# GateDriverSketch.net
KiCad netlist of a schematic drawn in Altium Designer
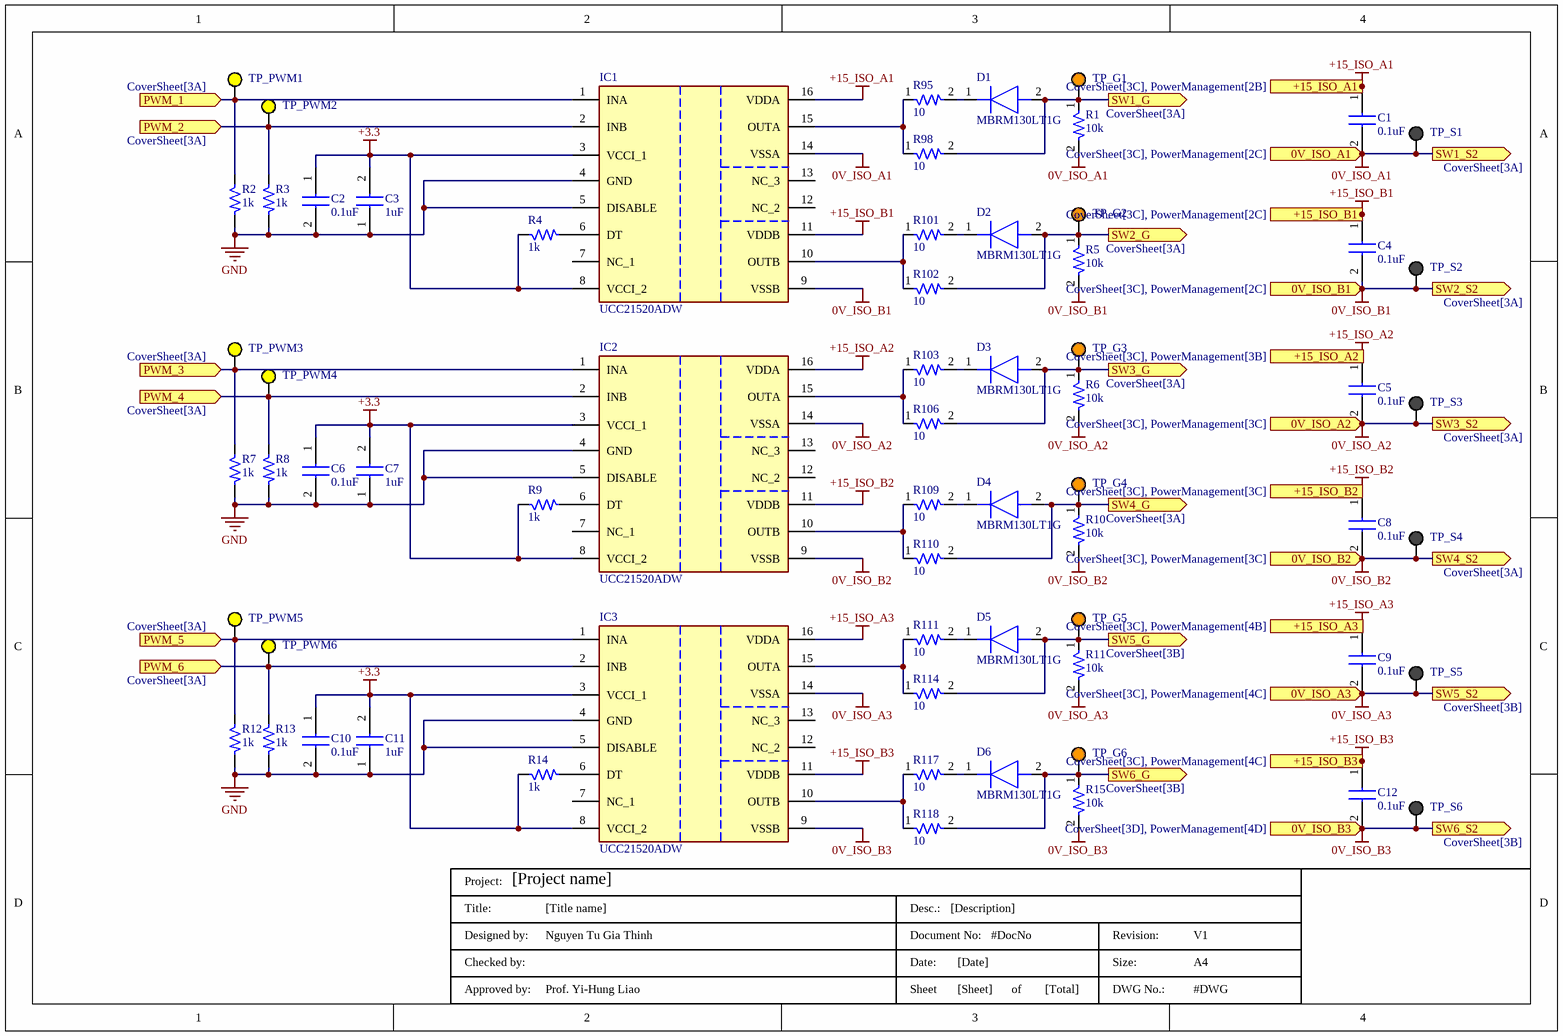
[diagram p0: GateDriverSketch.SchDoc]

(export (version "E")
  (design (tool "Eeschema 10.0.6"))
  (components
    (comp (ref "C1")
      (value "0.1uF")
      (footprint "SamacSys:C0805")
      (description "Capacitor")
      (fields
        (field (name "MANUFACTURER_PART_NUMBER") "C0805C104K3RACTU")
        (field (name "MOUSER PART NUMBER") "80-C0805C104K3R")
      )
      (libsource (lib "SamacSys") (part "C0805C104K3RACTU"))
    )
    (comp (ref "C2")
      (value "0.1uF")
      (footprint "SamacSys:C0805")
      (description "Capacitor")
      (fields
        (field (name "MANUFACTURER_PART_NUMBER") "C0805C104K3RACTU")
        (field (name "MOUSER PART NUMBER") "80-C0805C104K3R")
      )
      (libsource (lib "SamacSys") (part "C0805C104K3RACTU"))
    )
    (comp (ref "C3")
      (value "1uF")
      (footprint "CAPC2012X145N")
      (description "Capacitor")
      (fields
        (field (name "MANUFACTURER_PART_NUMBER") "GRM21BR71H105KA12L")
        (field (name "MOUSER PART NUMBER") "81-GRM21BR71H105KA2L")
      )
      (libsource (lib "ViennaRectifier") (part "GRM21BR71H105KA12L"))
    )
    (comp (ref "C4")
      (value "0.1uF")
      (footprint "SamacSys:C0805")
      (description "Capacitor")
      (fields
        (field (name "MANUFACTURER_PART_NUMBER") "C0805C104K3RACTU")
        (field (name "MOUSER PART NUMBER") "80-C0805C104K3R")
      )
      (libsource (lib "SamacSys") (part "C0805C104K3RACTU"))
    )
    (comp (ref "C5")
      (value "0.1uF")
      (footprint "SamacSys:C0805")
      (description "Capacitor")
      (fields
        (field (name "MANUFACTURER_PART_NUMBER") "C0805C104K3RACTU")
        (field (name "MOUSER PART NUMBER") "80-C0805C104K3R")
      )
      (libsource (lib "SamacSys") (part "C0805C104K3RACTU"))
    )
    (comp (ref "C6")
      (value "0.1uF")
      (footprint "SamacSys:C0805")
      (description "Capacitor")
      (fields
        (field (name "MANUFACTURER_PART_NUMBER") "C0805C104K3RACTU")
        (field (name "MOUSER PART NUMBER") "80-C0805C104K3R")
      )
      (libsource (lib "SamacSys") (part "C0805C104K3RACTU"))
    )
    (comp (ref "C7")
      (value "1uF")
      (footprint "CAPC2012X145N")
      (description "Capacitor")
      (fields
        (field (name "MANUFACTURER_PART_NUMBER") "GRM21BR71H105KA12L")
        (field (name "MOUSER PART NUMBER") "81-GRM21BR71H105KA2L")
      )
      (libsource (lib "ViennaRectifier") (part "GRM21BR71H105KA12L"))
    )
    (comp (ref "C8")
      (value "0.1uF")
      (footprint "SamacSys:C0805")
      (description "Capacitor")
      (fields
        (field (name "MANUFACTURER_PART_NUMBER") "C0805C104K3RACTU")
        (field (name "MOUSER PART NUMBER") "80-C0805C104K3R")
      )
      (libsource (lib "SamacSys") (part "C0805C104K3RACTU"))
    )
    (comp (ref "C9")
      (value "0.1uF")
      (footprint "SamacSys:C0805")
      (description "Capacitor")
      (fields
        (field (name "MANUFACTURER_PART_NUMBER") "C0805C104K3RACTU")
        (field (name "MOUSER PART NUMBER") "80-C0805C104K3R")
      )
      (libsource (lib "SamacSys") (part "C0805C104K3RACTU"))
    )
    (comp (ref "C10")
      (value "0.1uF")
      (footprint "SamacSys:C0805")
      (description "Capacitor")
      (fields
        (field (name "MANUFACTURER_PART_NUMBER") "C0805C104K3RACTU")
        (field (name "MOUSER PART NUMBER") "80-C0805C104K3R")
      )
      (libsource (lib "SamacSys") (part "C0805C104K3RACTU"))
    )
    (comp (ref "C11")
      (value "1uF")
      (footprint "CAPC2012X145N")
      (description "Capacitor")
      (fields
        (field (name "MANUFACTURER_PART_NUMBER") "GRM21BR71H105KA12L")
        (field (name "MOUSER PART NUMBER") "81-GRM21BR71H105KA2L")
      )
      (libsource (lib "ViennaRectifier") (part "GRM21BR71H105KA12L"))
    )
    (comp (ref "C12")
      (value "0.1uF")
      (footprint "SamacSys:C0805")
      (description "Capacitor")
      (fields
        (field (name "MANUFACTURER_PART_NUMBER") "C0805C104K3RACTU")
        (field (name "MOUSER PART NUMBER") "80-C0805C104K3R")
      )
      (libsource (lib "SamacSys") (part "C0805C104K3RACTU"))
    )
    (comp (ref "D1")
      (value "MBRM130LT1G")
      (footprint "SamacSys:MBRM130LT1G")
      (description "Diode")
      (fields (field (name "MOUSER PART NUMBER") "863-MBRM130LT1G"))
      (libsource (lib "SamacSys") (part "MBRM130LT1G"))
    )
    (comp (ref "D2")
      (value "MBRM130LT1G")
      (footprint "SamacSys:MBRM130LT1G")
      (description "Diode")
      (fields (field (name "MOUSER PART NUMBER") "863-MBRM130LT1G"))
      (libsource (lib "SamacSys") (part "MBRM130LT1G"))
    )
    (comp (ref "D3")
      (value "MBRM130LT1G")
      (footprint "SamacSys:MBRM130LT1G")
      (description "Diode")
      (fields (field (name "MOUSER PART NUMBER") "863-MBRM130LT1G"))
      (libsource (lib "SamacSys") (part "MBRM130LT1G"))
    )
    (comp (ref "D4")
      (value "MBRM130LT1G")
      (footprint "SamacSys:MBRM130LT1G")
      (description "Diode")
      (fields (field (name "MOUSER PART NUMBER") "863-MBRM130LT1G"))
      (libsource (lib "SamacSys") (part "MBRM130LT1G"))
    )
    (comp (ref "D5")
      (value "MBRM130LT1G")
      (footprint "SamacSys:MBRM130LT1G")
      (description "Diode")
      (fields (field (name "MOUSER PART NUMBER") "863-MBRM130LT1G"))
      (libsource (lib "SamacSys") (part "MBRM130LT1G"))
    )
    (comp (ref "D6")
      (value "MBRM130LT1G")
      (footprint "SamacSys:MBRM130LT1G")
      (description "Diode")
      (fields (field (name "MOUSER PART NUMBER") "863-MBRM130LT1G"))
      (libsource (lib "SamacSys") (part "MBRM130LT1G"))
    )
    (comp (ref "IC1")
      (value "UCC21520ADW")
      (footprint "SamacSys:SOIC127P1030X265-16N")
      (description "Integrated Circuit")
      (fields (field (name "MOUSER PART NUMBER") "595-UCC21520ADW"))
      (libsource (lib "ViennaRectifier") (part "UCC21520ADW"))
    )
    (comp (ref "IC2")
      (value "UCC21520ADW")
      (footprint "SamacSys:SOIC127P1030X265-16N")
      (description "Integrated Circuit")
      (fields (field (name "MOUSER PART NUMBER") "595-UCC21520ADW"))
      (libsource (lib "ViennaRectifier") (part "UCC21520ADW"))
    )
    (comp (ref "IC3")
      (value "UCC21520ADW")
      (footprint "SamacSys:SOIC127P1030X265-16N")
      (description "Integrated Circuit")
      (fields (field (name "MOUSER PART NUMBER") "595-UCC21520ADW"))
      (libsource (lib "ViennaRectifier") (part "UCC21520ADW"))
    )
    (comp (ref "R1")
      (value "10k")
      (footprint "RESC2012X50N")
      (description "Resistor")
      (fields
        (field (name "MANUFACTURER_PART_NUMBER") "CRCW0805470RFKEA")
        (field (name "MOUSER PART NUMBER") "71-CRCW0805-470-E3")
      )
      (libsource (lib "ViennaRectifier") (part "CRCW0805470RFKEA_1"))
    )
    (comp (ref "R2")
      (value "1k")
      (footprint "SM-1206")
      (description "Resistor 1/4W")
      (libsource (lib "ViennaRectifier") (part "R"))
    )
    (comp (ref "R3")
      (value "1k")
      (footprint "SM-1206")
      (description "Resistor 1/4W")
      (libsource (lib "ViennaRectifier") (part "R"))
    )
    (comp (ref "R4")
      (value "1k")
      (footprint "SM-1206")
      (description "Resistor 1/4W")
      (libsource (lib "ViennaRectifier") (part "R"))
    )
    (comp (ref "R5")
      (value "10k")
      (footprint "RESC2012X50N")
      (description "Resistor")
      (fields
        (field (name "MANUFACTURER_PART_NUMBER") "CRCW0805470RFKEA")
        (field (name "MOUSER PART NUMBER") "71-CRCW0805-470-E3")
      )
      (libsource (lib "ViennaRectifier") (part "CRCW0805470RFKEA_1"))
    )
    (comp (ref "R6")
      (value "10k")
      (footprint "RESC2012X50N")
      (description "Resistor")
      (fields
        (field (name "MANUFACTURER_PART_NUMBER") "CRCW0805470RFKEA")
        (field (name "MOUSER PART NUMBER") "71-CRCW0805-470-E3")
      )
      (libsource (lib "ViennaRectifier") (part "CRCW0805470RFKEA_1"))
    )
    (comp (ref "R7")
      (value "1k")
      (footprint "SM-1206")
      (description "Resistor 1/4W")
      (libsource (lib "ViennaRectifier") (part "R"))
    )
    (comp (ref "R8")
      (value "1k")
      (footprint "SM-1206")
      (description "Resistor 1/4W")
      (libsource (lib "ViennaRectifier") (part "R"))
    )
    (comp (ref "R9")
      (value "1k")
      (footprint "SM-1206")
      (description "Resistor 1/4W")
      (libsource (lib "ViennaRectifier") (part "R"))
    )
    (comp (ref "R10")
      (value "10k")
      (footprint "RESC2012X50N")
      (description "Resistor")
      (fields
        (field (name "MANUFACTURER_PART_NUMBER") "CRCW0805470RFKEA")
        (field (name "MOUSER PART NUMBER") "71-CRCW0805-470-E3")
      )
      (libsource (lib "ViennaRectifier") (part "CRCW0805470RFKEA_1"))
    )
    (comp (ref "R11")
      (value "10k")
      (footprint "RESC2012X50N")
      (description "Resistor")
      (fields
        (field (name "MANUFACTURER_PART_NUMBER") "CRCW0805470RFKEA")
        (field (name "MOUSER PART NUMBER") "71-CRCW0805-470-E3")
      )
      (libsource (lib "ViennaRectifier") (part "CRCW0805470RFKEA_1"))
    )
    (comp (ref "R12")
      (value "1k")
      (footprint "SM-1206")
      (description "Resistor 1/4W")
      (libsource (lib "ViennaRectifier") (part "R"))
    )
    (comp (ref "R13")
      (value "1k")
      (footprint "SM-1206")
      (description "Resistor 1/4W")
      (libsource (lib "ViennaRectifier") (part "R"))
    )
    (comp (ref "R14")
      (value "1k")
      (footprint "SM-1206")
      (description "Resistor 1/4W")
      (libsource (lib "ViennaRectifier") (part "R"))
    )
    (comp (ref "R15")
      (value "10k")
      (footprint "RESC2012X50N")
      (description "Resistor")
      (fields
        (field (name "MANUFACTURER_PART_NUMBER") "CRCW0805470RFKEA")
        (field (name "MOUSER PART NUMBER") "71-CRCW0805-470-E3")
      )
      (libsource (lib "ViennaRectifier") (part "CRCW0805470RFKEA_1"))
    )
    (comp (ref "R95")
      (value "10")
      (footprint "RESC2012X50N")
      (description "Resistor")
      (fields
        (field (name "MANUFACTURER_PART_NUMBER") "CRCW0805470RFKEA")
        (field (name "MOUSER PART NUMBER") "71-CRCW0805-470-E3")
      )
      (libsource (lib "ViennaRectifier") (part "CRCW0805470RFKEA_1"))
    )
    (comp (ref "R98")
      (value "10")
      (footprint "RESC2012X50N")
      (description "Resistor")
      (fields
        (field (name "MANUFACTURER_PART_NUMBER") "CRCW0805470RFKEA")
        (field (name "MOUSER PART NUMBER") "71-CRCW0805-470-E3")
      )
      (libsource (lib "ViennaRectifier") (part "CRCW0805470RFKEA_1"))
    )
    (comp (ref "R101")
      (value "10")
      (footprint "RESC2012X50N")
      (description "Resistor")
      (fields
        (field (name "MANUFACTURER_PART_NUMBER") "CRCW0805470RFKEA")
        (field (name "MOUSER PART NUMBER") "71-CRCW0805-470-E3")
      )
      (libsource (lib "ViennaRectifier") (part "CRCW0805470RFKEA_1"))
    )
    (comp (ref "R102")
      (value "10")
      (footprint "RESC2012X50N")
      (description "Resistor")
      (fields
        (field (name "MANUFACTURER_PART_NUMBER") "CRCW0805470RFKEA")
        (field (name "MOUSER PART NUMBER") "71-CRCW0805-470-E3")
      )
      (libsource (lib "ViennaRectifier") (part "CRCW0805470RFKEA_1"))
    )
    (comp (ref "R103")
      (value "10")
      (footprint "RESC2012X50N")
      (description "Resistor")
      (fields
        (field (name "MANUFACTURER_PART_NUMBER") "CRCW0805470RFKEA")
        (field (name "MOUSER PART NUMBER") "71-CRCW0805-470-E3")
      )
      (libsource (lib "ViennaRectifier") (part "CRCW0805470RFKEA_1"))
    )
    (comp (ref "R106")
      (value "10")
      (footprint "RESC2012X50N")
      (description "Resistor")
      (fields
        (field (name "MANUFACTURER_PART_NUMBER") "CRCW0805470RFKEA")
        (field (name "MOUSER PART NUMBER") "71-CRCW0805-470-E3")
      )
      (libsource (lib "ViennaRectifier") (part "CRCW0805470RFKEA_1"))
    )
    (comp (ref "R109")
      (value "10")
      (footprint "RESC2012X50N")
      (description "Resistor")
      (fields
        (field (name "MANUFACTURER_PART_NUMBER") "CRCW0805470RFKEA")
        (field (name "MOUSER PART NUMBER") "71-CRCW0805-470-E3")
      )
      (libsource (lib "ViennaRectifier") (part "CRCW0805470RFKEA_1"))
    )
    (comp (ref "R110")
      (value "10")
      (footprint "RESC2012X50N")
      (description "Resistor")
      (fields
        (field (name "MANUFACTURER_PART_NUMBER") "CRCW0805470RFKEA")
        (field (name "MOUSER PART NUMBER") "71-CRCW0805-470-E3")
      )
      (libsource (lib "ViennaRectifier") (part "CRCW0805470RFKEA_1"))
    )
    (comp (ref "R111")
      (value "10")
      (footprint "RESC2012X50N")
      (description "Resistor")
      (fields
        (field (name "MANUFACTURER_PART_NUMBER") "CRCW0805470RFKEA")
        (field (name "MOUSER PART NUMBER") "71-CRCW0805-470-E3")
      )
      (libsource (lib "ViennaRectifier") (part "CRCW0805470RFKEA_1"))
    )
    (comp (ref "R114")
      (value "10")
      (footprint "RESC2012X50N")
      (description "Resistor")
      (fields
        (field (name "MANUFACTURER_PART_NUMBER") "CRCW0805470RFKEA")
        (field (name "MOUSER PART NUMBER") "71-CRCW0805-470-E3")
      )
      (libsource (lib "ViennaRectifier") (part "CRCW0805470RFKEA_1"))
    )
    (comp (ref "R117")
      (value "10")
      (footprint "RESC2012X50N")
      (description "Resistor")
      (fields
        (field (name "MANUFACTURER_PART_NUMBER") "CRCW0805470RFKEA")
        (field (name "MOUSER PART NUMBER") "71-CRCW0805-470-E3")
      )
      (libsource (lib "ViennaRectifier") (part "CRCW0805470RFKEA_1"))
    )
    (comp (ref "R118")
      (value "10")
      (footprint "RESC2012X50N")
      (description "Resistor")
      (fields
        (field (name "MANUFACTURER_PART_NUMBER") "CRCW0805470RFKEA")
        (field (name "MOUSER PART NUMBER") "71-CRCW0805-470-E3")
      )
      (libsource (lib "ViennaRectifier") (part "CRCW0805470RFKEA_1"))
    )
    (comp (ref "TP_G1")
      (value "~")
      (footprint "5003")
      (description "Test Point Orrange, Multipurpose, TH")
      (libsource (lib "TestPointKeystone") (part "5003"))
    )
    (comp (ref "TP_G2")
      (value "~")
      (footprint "5003")
      (description "Test Point Orrange, Multipurpose, TH")
      (libsource (lib "TestPointKeystone") (part "5003"))
    )
    (comp (ref "TP_G3")
      (value "~")
      (footprint "5003")
      (description "Test Point Orrange, Multipurpose, TH")
      (libsource (lib "TestPointKeystone") (part "5003"))
    )
    (comp (ref "TP_G4")
      (value "~")
      (footprint "5003")
      (description "Test Point Orrange, Multipurpose, TH")
      (libsource (lib "TestPointKeystone") (part "5003"))
    )
    (comp (ref "TP_G5")
      (value "~")
      (footprint "5003")
      (description "Test Point Orrange, Multipurpose, TH")
      (libsource (lib "TestPointKeystone") (part "5003"))
    )
    (comp (ref "TP_G6")
      (value "~")
      (footprint "5003")
      (description "Test Point Orrange, Multipurpose, TH")
      (libsource (lib "TestPointKeystone") (part "5003"))
    )
    (comp (ref "TP_PWM1")
      (value "~")
      (footprint "5004")
      (description "Test Point Yellow, Multipurpose, TH")
      (libsource (lib "TestPointKeystone") (part "5004"))
    )
    (comp (ref "TP_PWM2")
      (value "~")
      (footprint "5004")
      (description "Test Point Yellow, Multipurpose, TH")
      (libsource (lib "TestPointKeystone") (part "5004"))
    )
    (comp (ref "TP_PWM3")
      (value "~")
      (footprint "5004")
      (description "Test Point Yellow, Multipurpose, TH")
      (libsource (lib "TestPointKeystone") (part "5004"))
    )
    (comp (ref "TP_PWM4")
      (value "~")
      (footprint "5004")
      (description "Test Point Yellow, Multipurpose, TH")
      (libsource (lib "TestPointKeystone") (part "5004"))
    )
    (comp (ref "TP_PWM5")
      (value "~")
      (footprint "5004")
      (description "Test Point Yellow, Multipurpose, TH")
      (libsource (lib "TestPointKeystone") (part "5004"))
    )
    (comp (ref "TP_PWM6")
      (value "~")
      (footprint "5004")
      (description "Test Point Yellow, Multipurpose, TH")
      (libsource (lib "TestPointKeystone") (part "5004"))
    )
    (comp (ref "TP_S1")
      (value "~")
      (footprint "5001")
      (description "Test Point Black, Multipurpose, TH")
      (libsource (lib "TestPointKeystone") (part "5001"))
    )
    (comp (ref "TP_S2")
      (value "~")
      (footprint "5001")
      (description "Test Point Black, Multipurpose, TH")
      (libsource (lib "TestPointKeystone") (part "5001"))
    )
    (comp (ref "TP_S3")
      (value "~")
      (footprint "5001")
      (description "Test Point Black, Multipurpose, TH")
      (libsource (lib "TestPointKeystone") (part "5001"))
    )
    (comp (ref "TP_S4")
      (value "~")
      (footprint "5001")
      (description "Test Point Black, Multipurpose, TH")
      (libsource (lib "TestPointKeystone") (part "5001"))
    )
    (comp (ref "TP_S5")
      (value "~")
      (footprint "5001")
      (description "Test Point Black, Multipurpose, TH")
      (libsource (lib "TestPointKeystone") (part "5001"))
    )
    (comp (ref "TP_S6")
      (value "~")
      (footprint "5001")
      (description "Test Point Black, Multipurpose, TH")
      (libsource (lib "TestPointKeystone") (part "5001"))
    )
  )
  (nets
    (net (code "2") (name "+15_ISO_A1") (class "Default")
      (node (ref "C1") (pin "1") (pinfunction "1_1") (pintype "passive"))
      (node (ref "IC1") (pin "16") (pinfunction "VDDA_16") (pintype "passive"))
    )
    (net (code "3") (name "+15_ISO_A2") (class "Default")
      (node (ref "C5") (pin "1") (pinfunction "1_1") (pintype "passive"))
      (node (ref "IC2") (pin "16") (pinfunction "VDDA_16") (pintype "passive"))
    )
    (net (code "4") (name "+15_ISO_A3") (class "Default")
      (node (ref "C9") (pin "1") (pinfunction "1_1") (pintype "passive"))
      (node (ref "IC3") (pin "16") (pinfunction "VDDA_16") (pintype "passive"))
    )
    (net (code "5") (name "+15_ISO_B1") (class "Default")
      (node (ref "C4") (pin "1") (pinfunction "1_1") (pintype "passive"))
      (node (ref "IC1") (pin "11") (pinfunction "VDDB_11") (pintype "passive"))
    )
    (net (code "6") (name "+15_ISO_B2") (class "Default")
      (node (ref "C8") (pin "1") (pinfunction "1_1") (pintype "passive"))
      (node (ref "IC2") (pin "11") (pinfunction "VDDB_11") (pintype "passive"))
    )
    (net (code "7") (name "+15_ISO_B3") (class "Default")
      (node (ref "C12") (pin "1") (pinfunction "1_1") (pintype "passive"))
      (node (ref "IC3") (pin "11") (pinfunction "VDDB_11") (pintype "passive"))
    )
    (net (code "8") (name "/PWM_1") (class "Default")
      (node (ref "IC1") (pin "1") (pinfunction "INA_1") (pintype "passive"))
      (node (ref "R2") (pin "1") (pinfunction "1_1") (pintype "passive"))
      (node (ref "TP_PWM1") (pin "1") (pinfunction "1_1") (pintype "passive"))
    )
    (net (code "9") (name "/PWM_2") (class "Default")
      (node (ref "IC1") (pin "2") (pinfunction "INB_2") (pintype "passive"))
      (node (ref "R3") (pin "1") (pinfunction "1_1") (pintype "passive"))
      (node (ref "TP_PWM2") (pin "1") (pinfunction "1_1") (pintype "passive"))
    )
    (net (code "10") (name "/PWM_3") (class "Default")
      (node (ref "IC2") (pin "1") (pinfunction "INA_1") (pintype "passive"))
      (node (ref "R7") (pin "1") (pinfunction "1_1") (pintype "passive"))
      (node (ref "TP_PWM3") (pin "1") (pinfunction "1_1") (pintype "passive"))
    )
    (net (code "11") (name "/PWM_4") (class "Default")
      (node (ref "IC2") (pin "2") (pinfunction "INB_2") (pintype "passive"))
      (node (ref "R8") (pin "1") (pinfunction "1_1") (pintype "passive"))
      (node (ref "TP_PWM4") (pin "1") (pinfunction "1_1") (pintype "passive"))
    )
    (net (code "12") (name "/PWM_5") (class "Default")
      (node (ref "IC3") (pin "1") (pinfunction "INA_1") (pintype "passive"))
      (node (ref "R12") (pin "1") (pinfunction "1_1") (pintype "passive"))
      (node (ref "TP_PWM5") (pin "1") (pinfunction "1_1") (pintype "passive"))
    )
    (net (code "13") (name "/PWM_6") (class "Default")
      (node (ref "IC3") (pin "2") (pinfunction "INB_2") (pintype "passive"))
      (node (ref "R13") (pin "1") (pinfunction "1_1") (pintype "passive"))
      (node (ref "TP_PWM6") (pin "1") (pinfunction "1_1") (pintype "passive"))
    )
    (net (code "14") (name "/SW1_G") (class "Default")
      (node (ref "D1") (pin "2") (pinfunction "A_2") (pintype "passive"))
      (node (ref "R1") (pin "1") (pinfunction "1_1") (pintype "passive"))
      (node (ref "R98") (pin "2") (pinfunction "2_2") (pintype "passive"))
      (node (ref "TP_G1") (pin "1") (pinfunction "1_1") (pintype "passive"))
    )
    (net (code "15") (name "/SW2_G") (class "Default")
      (node (ref "D2") (pin "2") (pinfunction "A_2") (pintype "passive"))
      (node (ref "R102") (pin "2") (pinfunction "2_2") (pintype "passive"))
      (node (ref "R5") (pin "1") (pinfunction "1_1") (pintype "passive"))
      (node (ref "TP_G2") (pin "1") (pinfunction "1_1") (pintype "passive"))
    )
    (net (code "16") (name "/SW3_G") (class "Default")
      (node (ref "D3") (pin "2") (pinfunction "A_2") (pintype "passive"))
      (node (ref "R106") (pin "2") (pinfunction "2_2") (pintype "passive"))
      (node (ref "R6") (pin "1") (pinfunction "1_1") (pintype "passive"))
      (node (ref "TP_G3") (pin "1") (pinfunction "1_1") (pintype "passive"))
    )
    (net (code "17") (name "/SW4_G") (class "Default")
      (node (ref "D4") (pin "2") (pinfunction "A_2") (pintype "passive"))
      (node (ref "R10") (pin "1") (pinfunction "1_1") (pintype "passive"))
      (node (ref "R110") (pin "2") (pinfunction "2_2") (pintype "passive"))
      (node (ref "TP_G4") (pin "1") (pinfunction "1_1") (pintype "passive"))
    )
    (net (code "18") (name "/SW5_G") (class "Default")
      (node (ref "D5") (pin "2") (pinfunction "A_2") (pintype "passive"))
      (node (ref "R11") (pin "1") (pinfunction "1_1") (pintype "passive"))
      (node (ref "R114") (pin "2") (pinfunction "2_2") (pintype "passive"))
      (node (ref "TP_G5") (pin "1") (pinfunction "1_1") (pintype "passive"))
    )
    (net (code "19") (name "/SW6_G") (class "Default")
      (node (ref "D6") (pin "2") (pinfunction "A_2") (pintype "passive"))
      (node (ref "R118") (pin "2") (pinfunction "2_2") (pintype "passive"))
      (node (ref "R15") (pin "1") (pinfunction "1_1") (pintype "passive"))
      (node (ref "TP_G6") (pin "1") (pinfunction "1_1") (pintype "passive"))
    )
    (net (code "20") (name "0V_ISO_A1") (class "Default")
      (node (ref "C1") (pin "2") (pinfunction "2_2") (pintype "passive"))
      (node (ref "IC1") (pin "14") (pinfunction "VSSA_14") (pintype "passive"))
      (node (ref "R1") (pin "2") (pinfunction "2_2") (pintype "passive"))
      (node (ref "TP_S1") (pin "1") (pinfunction "1_1") (pintype "passive"))
    )
    (net (code "21") (name "0V_ISO_A2") (class "Default")
      (node (ref "C5") (pin "2") (pinfunction "2_2") (pintype "passive"))
      (node (ref "IC2") (pin "14") (pinfunction "VSSA_14") (pintype "passive"))
      (node (ref "R6") (pin "2") (pinfunction "2_2") (pintype "passive"))
      (node (ref "TP_S3") (pin "1") (pinfunction "1_1") (pintype "passive"))
    )
    (net (code "22") (name "0V_ISO_A3") (class "Default")
      (node (ref "C9") (pin "2") (pinfunction "2_2") (pintype "passive"))
      (node (ref "IC3") (pin "14") (pinfunction "VSSA_14") (pintype "passive"))
      (node (ref "R11") (pin "2") (pinfunction "2_2") (pintype "passive"))
      (node (ref "TP_S5") (pin "1") (pinfunction "1_1") (pintype "passive"))
    )
    (net (code "23") (name "0V_ISO_B1") (class "Default")
      (node (ref "C4") (pin "2") (pinfunction "2_2") (pintype "passive"))
      (node (ref "IC1") (pin "9") (pinfunction "VSSB_9") (pintype "passive"))
      (node (ref "R5") (pin "2") (pinfunction "2_2") (pintype "passive"))
      (node (ref "TP_S2") (pin "1") (pinfunction "1_1") (pintype "passive"))
    )
    (net (code "24") (name "0V_ISO_B2") (class "Default")
      (node (ref "C8") (pin "2") (pinfunction "2_2") (pintype "passive"))
      (node (ref "IC2") (pin "9") (pinfunction "VSSB_9") (pintype "passive"))
      (node (ref "R10") (pin "2") (pinfunction "2_2") (pintype "passive"))
      (node (ref "TP_S4") (pin "1") (pinfunction "1_1") (pintype "passive"))
    )
    (net (code "25") (name "0V_ISO_B3") (class "Default")
      (node (ref "C12") (pin "2") (pinfunction "2_2") (pintype "passive"))
      (node (ref "IC3") (pin "9") (pinfunction "VSSB_9") (pintype "passive"))
      (node (ref "R15") (pin "2") (pinfunction "2_2") (pintype "passive"))
      (node (ref "TP_S6") (pin "1") (pinfunction "1_1") (pintype "passive"))
    )
    (net (code "26") (name "GND") (class "Default")
      (node (ref "C10") (pin "2") (pinfunction "2_2") (pintype "passive"))
      (node (ref "C11") (pin "1") (pinfunction "1_1") (pintype "passive"))
      (node (ref "C2") (pin "2") (pinfunction "2_2") (pintype "passive"))
      (node (ref "C3") (pin "1") (pinfunction "1_1") (pintype "passive"))
      (node (ref "C6") (pin "2") (pinfunction "2_2") (pintype "passive"))
      (node (ref "C7") (pin "1") (pinfunction "1_1") (pintype "passive"))
      (node (ref "IC1") (pin "4") (pinfunction "GND_4") (pintype "passive"))
      (node (ref "IC1") (pin "5") (pinfunction "DISABLE_5") (pintype "passive"))
      (node (ref "IC2") (pin "4") (pinfunction "GND_4") (pintype "passive"))
      (node (ref "IC2") (pin "5") (pinfunction "DISABLE_5") (pintype "passive"))
      (node (ref "IC3") (pin "4") (pinfunction "GND_4") (pintype "passive"))
      (node (ref "IC3") (pin "5") (pinfunction "DISABLE_5") (pintype "passive"))
      (node (ref "R12") (pin "2") (pinfunction "2_2") (pintype "passive"))
      (node (ref "R13") (pin "2") (pinfunction "2_2") (pintype "passive"))
      (node (ref "R2") (pin "2") (pinfunction "2_2") (pintype "passive"))
      (node (ref "R3") (pin "2") (pinfunction "2_2") (pintype "passive"))
      (node (ref "R7") (pin "2") (pinfunction "2_2") (pintype "passive"))
      (node (ref "R8") (pin "2") (pinfunction "2_2") (pintype "passive"))
    )
    (net (code "27") (name "Net-(D1-K)") (class "Default")
      (node (ref "D1") (pin "1") (pinfunction "K_1") (pintype "passive"))
      (node (ref "R95") (pin "2") (pinfunction "2_2") (pintype "passive"))
    )
    (net (code "28") (name "Net-(D2-K)") (class "Default")
      (node (ref "D2") (pin "1") (pinfunction "K_1") (pintype "passive"))
      (node (ref "R101") (pin "2") (pinfunction "2_2") (pintype "passive"))
    )
    (net (code "29") (name "Net-(D3-K)") (class "Default")
      (node (ref "D3") (pin "1") (pinfunction "K_1") (pintype "passive"))
      (node (ref "R103") (pin "2") (pinfunction "2_2") (pintype "passive"))
    )
    (net (code "30") (name "Net-(D4-K)") (class "Default")
      (node (ref "D4") (pin "1") (pinfunction "K_1") (pintype "passive"))
      (node (ref "R109") (pin "2") (pinfunction "2_2") (pintype "passive"))
    )
    (net (code "31") (name "Net-(D5-K)") (class "Default")
      (node (ref "D5") (pin "1") (pinfunction "K_1") (pintype "passive"))
      (node (ref "R111") (pin "2") (pinfunction "2_2") (pintype "passive"))
    )
    (net (code "32") (name "Net-(D6-K)") (class "Default")
      (node (ref "D6") (pin "1") (pinfunction "K_1") (pintype "passive"))
      (node (ref "R117") (pin "2") (pinfunction "2_2") (pintype "passive"))
    )
    (net (code "33") (name "Net-(IC1-DT)") (class "Default")
      (node (ref "IC1") (pin "6") (pinfunction "DT_6") (pintype "passive"))
      (node (ref "R4") (pin "2") (pinfunction "2_2") (pintype "passive"))
    )
    (net (code "34") (name "Net-(IC1-OUTA)") (class "Default")
      (node (ref "IC1") (pin "15") (pinfunction "OUTA_15") (pintype "passive"))
      (node (ref "R95") (pin "1") (pinfunction "1_1") (pintype "passive"))
      (node (ref "R98") (pin "1") (pinfunction "1_1") (pintype "passive"))
    )
    (net (code "35") (name "Net-(IC1-OUTB)") (class "Default")
      (node (ref "IC1") (pin "10") (pinfunction "OUTB_10") (pintype "passive"))
      (node (ref "R101") (pin "1") (pinfunction "1_1") (pintype "passive"))
      (node (ref "R102") (pin "1") (pinfunction "1_1") (pintype "passive"))
    )
    (net (code "36") (name "Net-(IC1-VCCI_1)") (class "Default")
      (node (ref "C2") (pin "1") (pinfunction "1_1") (pintype "passive"))
      (node (ref "C3") (pin "2") (pinfunction "2_2") (pintype "passive"))
      (node (ref "IC1") (pin "3") (pinfunction "VCCI_1_3") (pintype "passive"))
      (node (ref "IC1") (pin "8") (pinfunction "VCCI_2_8") (pintype "passive"))
      (node (ref "R4") (pin "1") (pinfunction "1_1") (pintype "passive"))
    )
    (net (code "37") (name "Net-(IC2-DT)") (class "Default")
      (node (ref "IC2") (pin "6") (pinfunction "DT_6") (pintype "passive"))
      (node (ref "R9") (pin "2") (pinfunction "2_2") (pintype "passive"))
    )
    (net (code "38") (name "Net-(IC2-OUTA)") (class "Default")
      (node (ref "IC2") (pin "15") (pinfunction "OUTA_15") (pintype "passive"))
      (node (ref "R103") (pin "1") (pinfunction "1_1") (pintype "passive"))
      (node (ref "R106") (pin "1") (pinfunction "1_1") (pintype "passive"))
    )
    (net (code "39") (name "Net-(IC2-OUTB)") (class "Default")
      (node (ref "IC2") (pin "10") (pinfunction "OUTB_10") (pintype "passive"))
      (node (ref "R109") (pin "1") (pinfunction "1_1") (pintype "passive"))
      (node (ref "R110") (pin "1") (pinfunction "1_1") (pintype "passive"))
    )
    (net (code "40") (name "Net-(IC2-VCCI_1)") (class "Default")
      (node (ref "C6") (pin "1") (pinfunction "1_1") (pintype "passive"))
      (node (ref "C7") (pin "2") (pinfunction "2_2") (pintype "passive"))
      (node (ref "IC2") (pin "3") (pinfunction "VCCI_1_3") (pintype "passive"))
      (node (ref "IC2") (pin "8") (pinfunction "VCCI_2_8") (pintype "passive"))
      (node (ref "R9") (pin "1") (pinfunction "1_1") (pintype "passive"))
    )
    (net (code "41") (name "Net-(IC3-DT)") (class "Default")
      (node (ref "IC3") (pin "6") (pinfunction "DT_6") (pintype "passive"))
      (node (ref "R14") (pin "2") (pinfunction "2_2") (pintype "passive"))
    )
    (net (code "42") (name "Net-(IC3-OUTA)") (class "Default")
      (node (ref "IC3") (pin "15") (pinfunction "OUTA_15") (pintype "passive"))
      (node (ref "R111") (pin "1") (pinfunction "1_1") (pintype "passive"))
      (node (ref "R114") (pin "1") (pinfunction "1_1") (pintype "passive"))
    )
    (net (code "43") (name "Net-(IC3-OUTB)") (class "Default")
      (node (ref "IC3") (pin "10") (pinfunction "OUTB_10") (pintype "passive"))
      (node (ref "R117") (pin "1") (pinfunction "1_1") (pintype "passive"))
      (node (ref "R118") (pin "1") (pinfunction "1_1") (pintype "passive"))
    )
    (net (code "44") (name "Net-(IC3-VCCI_1)") (class "Default")
      (node (ref "C10") (pin "1") (pinfunction "1_1") (pintype "passive"))
      (node (ref "C11") (pin "2") (pinfunction "2_2") (pintype "passive"))
      (node (ref "IC3") (pin "3") (pinfunction "VCCI_1_3") (pintype "passive"))
      (node (ref "IC3") (pin "8") (pinfunction "VCCI_2_8") (pintype "passive"))
      (node (ref "R14") (pin "1") (pinfunction "1_1") (pintype "passive"))
    )
    (net (code "45") (name "unconnected-(IC1-NC_1-Pad7)") (class "Default")
      (node (ref "IC1") (pin "7") (pinfunction "NC_1_7") (pintype "passive"))
    )
    (net (code "46") (name "unconnected-(IC1-NC_2-Pad12)") (class "Default")
      (node (ref "IC1") (pin "12") (pinfunction "NC_2_12") (pintype "passive"))
    )
    (net (code "47") (name "unconnected-(IC1-NC_3-Pad13)") (class "Default")
      (node (ref "IC1") (pin "13") (pinfunction "NC_3_13") (pintype "passive"))
    )
    (net (code "48") (name "unconnected-(IC2-NC_1-Pad7)") (class "Default")
      (node (ref "IC2") (pin "7") (pinfunction "NC_1_7") (pintype "passive"))
    )
    (net (code "49") (name "unconnected-(IC2-NC_2-Pad12)") (class "Default")
      (node (ref "IC2") (pin "12") (pinfunction "NC_2_12") (pintype "passive"))
    )
    (net (code "50") (name "unconnected-(IC2-NC_3-Pad13)") (class "Default")
      (node (ref "IC2") (pin "13") (pinfunction "NC_3_13") (pintype "passive"))
    )
    (net (code "51") (name "unconnected-(IC3-NC_1-Pad7)") (class "Default")
      (node (ref "IC3") (pin "7") (pinfunction "NC_1_7") (pintype "passive"))
    )
    (net (code "52") (name "unconnected-(IC3-NC_2-Pad12)") (class "Default")
      (node (ref "IC3") (pin "12") (pinfunction "NC_2_12") (pintype "passive"))
    )
    (net (code "53") (name "unconnected-(IC3-NC_3-Pad13)") (class "Default")
      (node (ref "IC3") (pin "13") (pinfunction "NC_3_13") (pintype "passive"))
    )
  )
)
